# SAMV71_Xplained_Ultra_Audio.net
KiCad netlist of a schematic drawn in Altium Designer
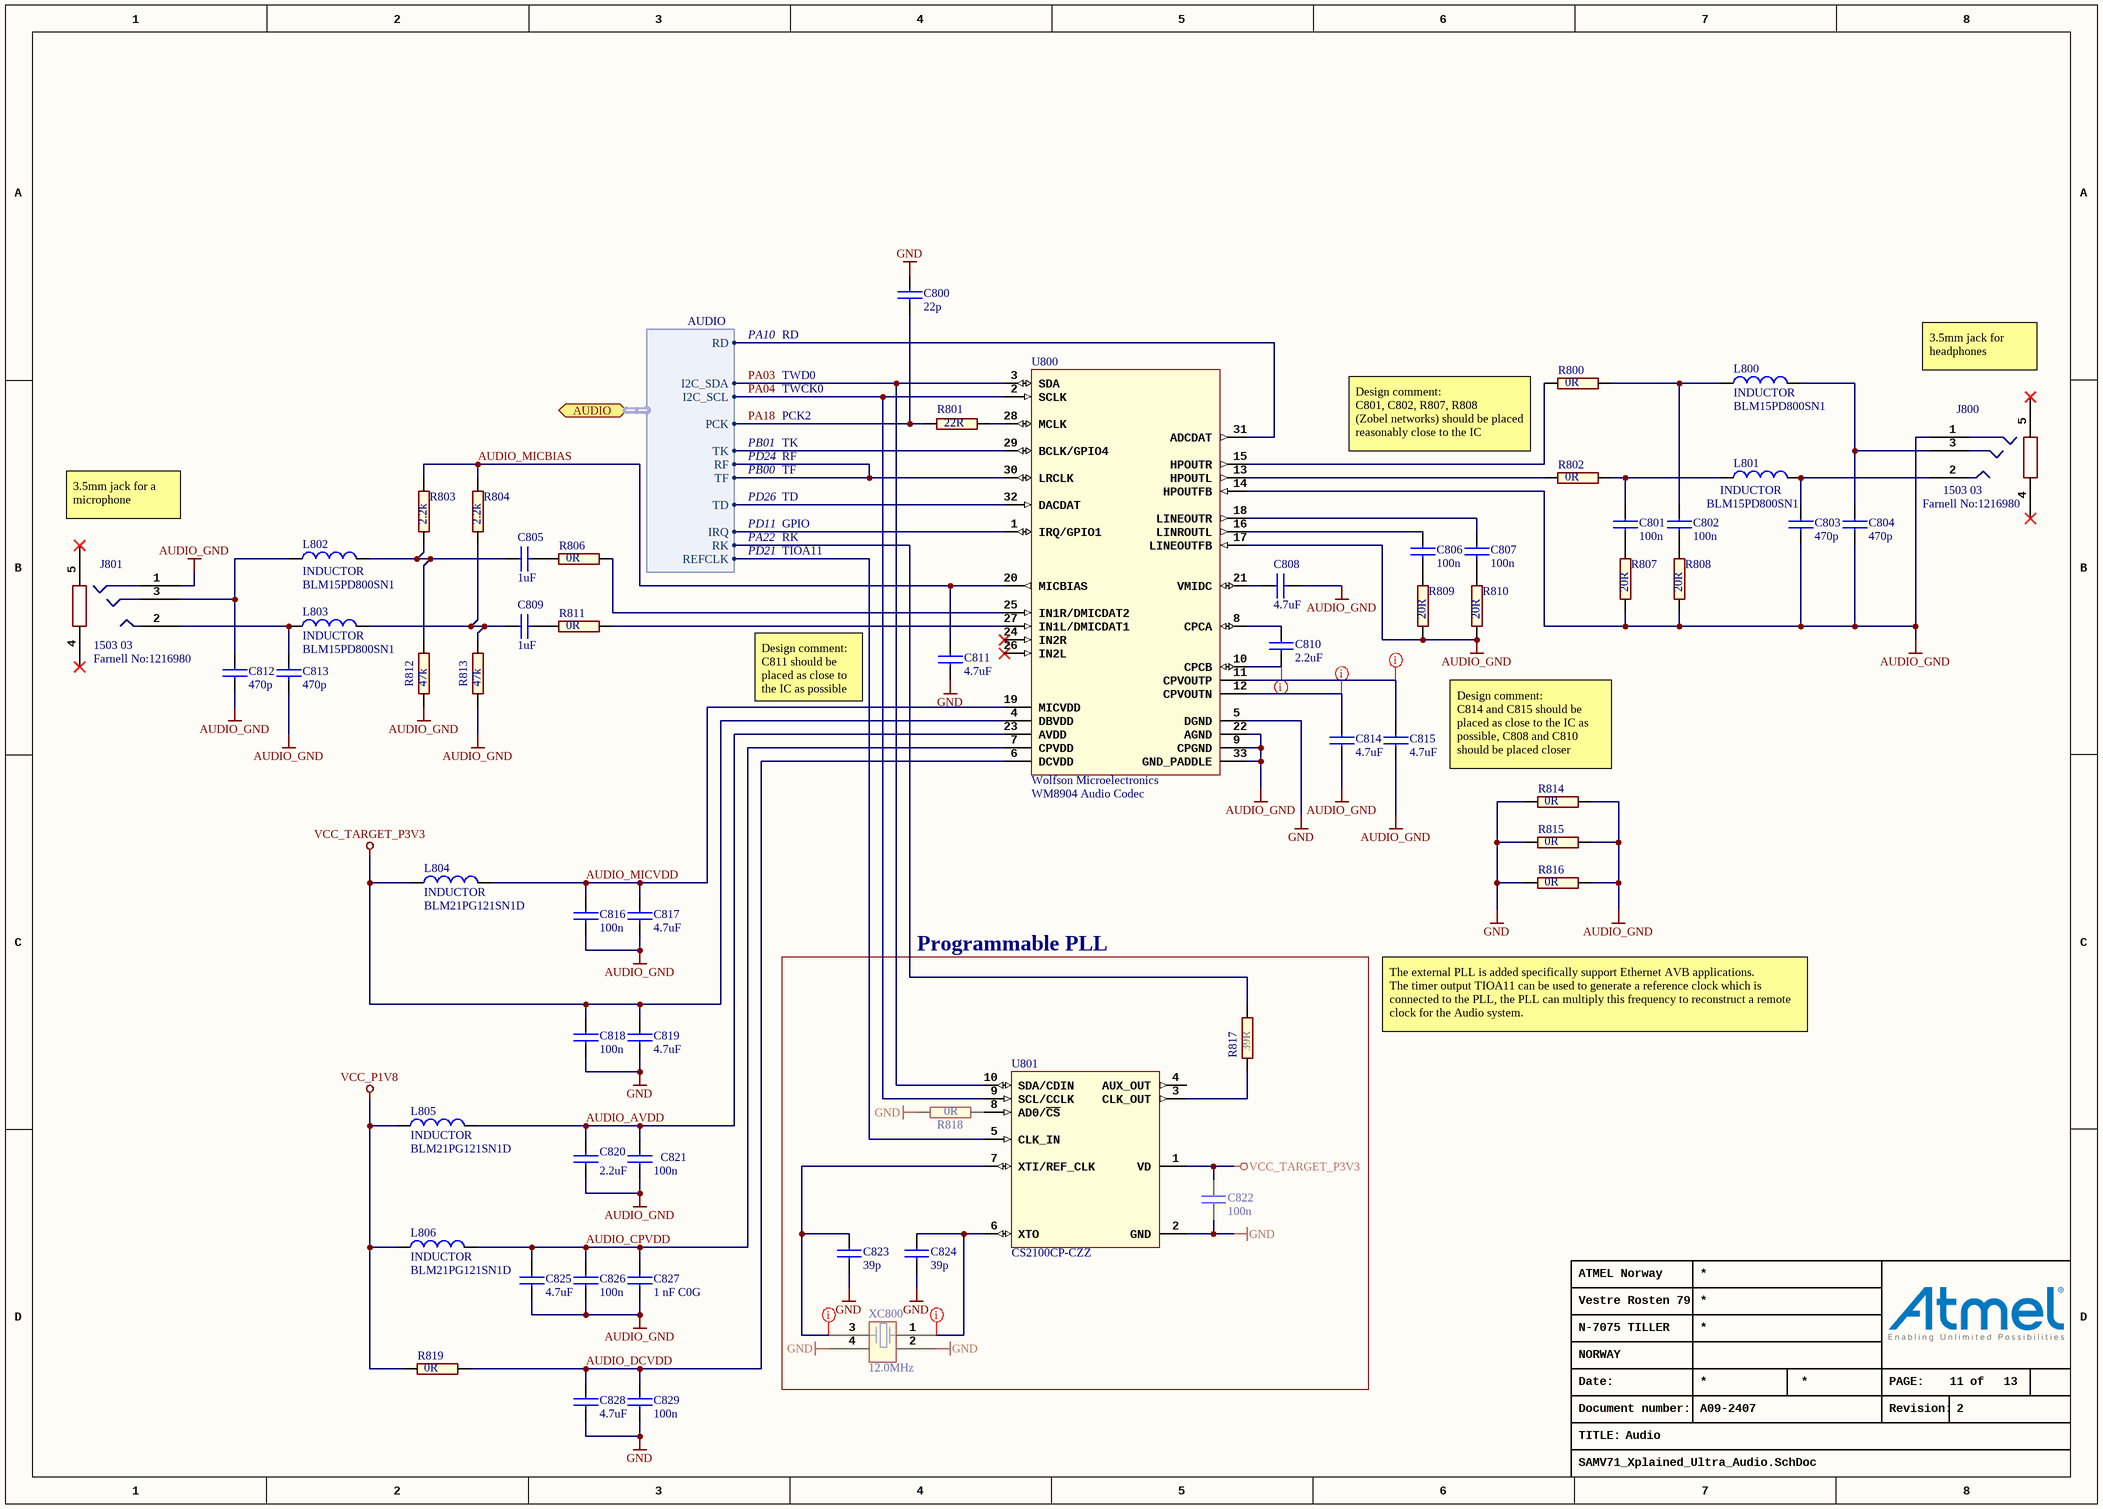
[diagram p0: SAMV71_Xplained_Ultra_Audio.SchDoc]

(export (version "E")
  (design (tool "Eeschema 10.0.6"))
  (components
    (comp (ref "C800")
      (value "22p")
      (footprint "AP1-00001")
      (description "Ceramic capacitor, SMD 0402, NP0, 50V, +/-5%")
      (fields (field (name "TOLERANCE") "50V, +/-5%") (field (name "Comment") "CAP-NONPOL"))
      (libsource (lib "AltiumDbLib") (part "CAP-NONPOL"))
    )
    (comp (ref "C801")
      (value "100n")
      (footprint "AP1-00001")
      (description "Ceramic capacitor, SMD 0402, X7R, 16V, +/-10%")
      (fields (field (name "TOLERANCE") "16V, +/-10%") (field (name "MANUFACTURER") "Kemet"))
      (libsource (lib "AltiumDbLib") (part "CAP-NONPOL"))
    )
    (comp (ref "C802")
      (value "100n")
      (footprint "AP1-00001")
      (description "Ceramic capacitor, SMD 0402, X7R, 16V, +/-10%")
      (fields (field (name "TOLERANCE") "16V, +/-10%") (field (name "MANUFACTURER") "Kemet"))
      (libsource (lib "AltiumDbLib") (part "CAP-NONPOL"))
    )
    (comp (ref "C803")
      (value "470p")
      (footprint "AP1-00001")
      (description "Ceramic capacitor, SMD 0402, X7R, 50V, +/-10%")
      (fields (field (name "TOLERANCE") "50V, +/-10%") (field (name "Comment") "8819904  @ element14"))
      (libsource (lib "AltiumDbLib") (part "CAP-NONPOL"))
    )
    (comp (ref "C804")
      (value "470p")
      (footprint "AP1-00001")
      (description "Ceramic capacitor, SMD 0402, X7R, 50V, +/-10%")
      (fields (field (name "TOLERANCE") "50V, +/-10%") (field (name "Comment") "8819904  @ element14"))
      (libsource (lib "AltiumDbLib") (part "CAP-NONPOL"))
    )
    (comp (ref "C805")
      (value "1uF")
      (footprint "AP1-00038")
      (description "Ceramic capacitor, SMD 0402, X5R, 10V, ±10 %")
      (fields (field (name "MANUFACTURER") "AVX") (field (name "MPN") "0402ZD105KAT2A"))
      (libsource (lib "AltiumDbLib") (part "CAP-NONPOL"))
    )
    (comp (ref "C806")
      (value "100n")
      (footprint "AP1-00001")
      (description "Ceramic capacitor, SMD 0402, X7R, 16V, +/-10%")
      (fields (field (name "TOLERANCE") "16V, +/-10%") (field (name "MANUFACTURER") "Kemet"))
      (libsource (lib "AltiumDbLib") (part "CAP-NONPOL"))
    )
    (comp (ref "C807")
      (value "100n")
      (footprint "AP1-00001")
      (description "Ceramic capacitor, SMD 0402, X7R, 16V, +/-10%")
      (fields (field (name "TOLERANCE") "16V, +/-10%") (field (name "MANUFACTURER") "Kemet"))
      (libsource (lib "AltiumDbLib") (part "CAP-NONPOL"))
    )
    (comp (ref "C808")
      (value "4.7uF")
      (footprint "AP1-00039")
      (description "Ceramic capacitor, SMD 0603, X5R, 10V, 10% (de31036)")
      (fields (field (name "TOLERANCE") "10%") (field (name "MANUFACTURER") "tdk"))
      (libsource (lib "AltiumDbLib") (part "CAP-NONPOL"))
    )
    (comp (ref "C809")
      (value "1uF")
      (footprint "AP1-00038")
      (description "Ceramic capacitor, SMD 0402, X5R, 10V, ±10 %")
      (fields (field (name "MANUFACTURER") "AVX") (field (name "MPN") "0402ZD105KAT2A"))
      (libsource (lib "AltiumDbLib") (part "CAP-NONPOL"))
    )
    (comp (ref "C810")
      (value "2.2uF")
      (footprint "AP1-00001")
      (description "Ceramic capacitor, SMD 0402, X5R, 6.3V, +/-20%")
      (fields (field (name "TOLERANCE") "Â±20%") (field (name "MANUFACTURER") "Kemet"))
      (libsource (lib "AltiumDbLib") (part "CAP-NONPOL"))
    )
    (comp (ref "C811")
      (value "4.7uF")
      (footprint "AP1-00039")
      (description "Ceramic capacitor, SMD 0603, X5R, 10V, 10% (de31036)")
      (fields (field (name "TOLERANCE") "10%") (field (name "MANUFACTURER") "tdk"))
      (libsource (lib "AltiumDbLib") (part "CAP-NONPOL"))
    )
    (comp (ref "C812")
      (value "470p")
      (footprint "AP1-00001")
      (description "Ceramic capacitor, SMD 0402, X7R, 50V, +/-10%")
      (fields (field (name "TOLERANCE") "50V, +/-10%") (field (name "Comment") "CAP-NONPOL"))
      (libsource (lib "AltiumDbLib") (part "CAP-NONPOL"))
    )
    (comp (ref "C813")
      (value "470p")
      (footprint "AP1-00001")
      (description "Ceramic capacitor, SMD 0402, X7R, 50V, +/-10%")
      (fields (field (name "TOLERANCE") "50V, +/-10%") (field (name "Comment") "CAP-NONPOL"))
      (libsource (lib "AltiumDbLib") (part "CAP-NONPOL"))
    )
    (comp (ref "C814")
      (value "4.7uF")
      (footprint "AP1-00001")
      (description "Ceramic capacitor, SMD 0402, X5R, 6.3V, +/-20% (de33687)")
      (fields (field (name "TOLERANCE") "+-20%") (field (name "MANUFACTURER") "Murata"))
      (libsource (lib "AltiumDbLib") (part "CAP-NONPOL"))
    )
    (comp (ref "C815")
      (value "4.7uF")
      (footprint "AP1-00001")
      (description "Ceramic capacitor, SMD 0402, X5R, 6.3V, +/-20% (de33687)")
      (fields (field (name "TOLERANCE") "+-20%") (field (name "MANUFACTURER") "Murata"))
      (libsource (lib "AltiumDbLib") (part "CAP-NONPOL"))
    )
    (comp (ref "C816")
      (value "100n")
      (footprint "AP1-00001")
      (description "Ceramic capacitor, SMD 0402, X7R, 16V, +/-10%")
      (fields (field (name "TOLERANCE") "16V, +/-10%") (field (name "MANUFACTURER") "Kemet"))
      (libsource (lib "AltiumDbLib") (part "CAP-NONPOL"))
    )
    (comp (ref "C817")
      (value "4.7uF")
      (footprint "AP1-00039")
      (description "Ceramic capacitor, SMD 0603, X5R, 10V, 10% (de31036)")
      (fields (field (name "TOLERANCE") "10%") (field (name "MANUFACTURER") "tdk"))
      (libsource (lib "AltiumDbLib") (part "CAP-NONPOL"))
    )
    (comp (ref "C818")
      (value "100n")
      (footprint "AP1-00001")
      (description "Ceramic capacitor, SMD 0402, X7R, 16V, +/-10%")
      (fields (field (name "TOLERANCE") "16V, +/-10%") (field (name "MANUFACTURER") "Kemet"))
      (libsource (lib "AltiumDbLib") (part "CAP-NONPOL"))
    )
    (comp (ref "C819")
      (value "4.7uF")
      (footprint "AP1-00039")
      (description "Ceramic capacitor, SMD 0603, X5R, 10V, 10% (de31036)")
      (fields (field (name "TOLERANCE") "10%") (field (name "MANUFACTURER") "tdk"))
      (libsource (lib "AltiumDbLib") (part "CAP-NONPOL"))
    )
    (comp (ref "C820")
      (value "2.2uF")
      (footprint "AP1-00001")
      (description "Ceramic capacitor, SMD 0402, X5R, 6.3V, +/-20%")
      (fields (field (name "TOLERANCE") "Â±20%") (field (name "MANUFACTURER") "Kemet"))
      (libsource (lib "AltiumDbLib") (part "CAP-NONPOL"))
    )
    (comp (ref "C821")
      (value "100n")
      (footprint "AP1-00001")
      (description "Ceramic capacitor, SMD 0402, X7R, 16V, +/-10%")
      (fields (field (name "TOLERANCE") "16V, +/-10%") (field (name "MANUFACTURER") "Kemet"))
      (libsource (lib "AltiumDbLib") (part "CAP-NONPOL"))
    )
    (comp (ref "C822")
      (value "100n")
      (footprint "AP1-00001")
      (description "Ceramic capacitor, SMD 0402, X7R, 16V, +/-10%")
      (fields (field (name "TOLERANCE") "16V, +/-10%") (field (name "MANUFACTURER") "Kemet"))
      (libsource (lib "AltiumDbLib") (part "CAP-NONPOL"))
    )
    (comp (ref "C823")
      (value "39p")
      (footprint "AP1-00001")
      (description "Ceramic capacitor, SMD 0402, NP0, 50V, +/-5%")
      (fields (field (name "TOLERANCE") "50V, +/-5%") (field (name "Comment") "CAP-NONPOL"))
      (libsource (lib "AltiumDbLib") (part "CAP-NONPOL"))
    )
    (comp (ref "C824")
      (value "39p")
      (footprint "AP1-00001")
      (description "Ceramic capacitor, SMD 0402, NP0, 50V, +/-5%")
      (fields (field (name "TOLERANCE") "50V, +/-5%") (field (name "Comment") "CAP-NONPOL"))
      (libsource (lib "AltiumDbLib") (part "CAP-NONPOL"))
    )
    (comp (ref "C825")
      (value "4.7uF")
      (footprint "AP1-00039")
      (description "Ceramic capacitor, SMD 0603, X5R, 10V, 10% (de31036)")
      (fields (field (name "TOLERANCE") "10%") (field (name "MANUFACTURER") "tdk"))
      (libsource (lib "AltiumDbLib") (part "CAP-NONPOL"))
    )
    (comp (ref "C826")
      (value "100n")
      (footprint "AP1-00001")
      (description "Ceramic capacitor, SMD 0402, X7R, 16V, +/-10%")
      (fields (field (name "TOLERANCE") "16V, +/-10%") (field (name "MANUFACTURER") "Kemet"))
      (libsource (lib "AltiumDbLib") (part "CAP-NONPOL"))
    )
    (comp (ref "C827")
      (value "1 nF C0G")
      (footprint "AP1-00001")
      (description "Ceramic capacitor, SMD 0402, C0G, 50V, +/-5%")
      (fields (field (name "TOLERANCE") "5%") (field (name "MANUFACTURER") "Murata"))
      (libsource (lib "AltiumDbLib") (part "CAP-NONPOL"))
    )
    (comp (ref "C828")
      (value "4.7uF")
      (footprint "AP1-00039")
      (description "Ceramic capacitor, SMD 0603, X5R, 10V, 10% (de31036)")
      (fields (field (name "TOLERANCE") "10%") (field (name "MANUFACTURER") "tdk"))
      (libsource (lib "AltiumDbLib") (part "CAP-NONPOL"))
    )
    (comp (ref "C829")
      (value "100n")
      (footprint "AP1-00001")
      (description "Ceramic capacitor, SMD 0402, X7R, 16V, +/-10%")
      (fields (field (name "TOLERANCE") "16V, +/-10%") (field (name "MANUFACTURER") "Kemet"))
      (libsource (lib "AltiumDbLib") (part "CAP-NONPOL"))
    )
    (comp (ref "J800")
      (value "Farnell No:1216980")
      (footprint "AP8-00397")
      (description "3.5mm stereo phone jack")
      (fields
        (field (name "ALTIUM_VALUE") "1503 03")
        (field (name "MANUFACTURER") "Lumberg")
        (field (name "MPN") "1503 03")
      )
      (libsource (lib "AltiumDbLib") (part "Jack_Stereo_1503_03"))
    )
    (comp (ref "J801")
      (value "Farnell No:1216980")
      (footprint "AP8-00397")
      (description "3.5mm stereo phone jack")
      (fields
        (field (name "ALTIUM_VALUE") "1503 03")
        (field (name "MANUFACTURER") "Lumberg")
        (field (name "MPN") "1503 03")
      )
      (libsource (lib "") (part "Jack_Stereo_1503_03_1"))
    )
    (comp (ref "L800")
      (value "INDUCTOR")
      (footprint "AP3-00028")
      (description "FERRITE CHIP 80 OHM 1500MA 0402")
      (fields
        (field (name "ALTIUM_VALUE") "BLM15PD800SN1")
        (field (name "TOLERANCE") "±25%")
        (field (name "MANUFACTURER") "Murata")
      )
      (libsource (lib "AltiumDbLib") (part "INDUCTOR"))
    )
    (comp (ref "L801")
      (value "INDUCTOR")
      (footprint "AP3-00028")
      (description "FERRITE CHIP 80 OHM 1500MA 0402")
      (fields
        (field (name "ALTIUM_VALUE") "BLM15PD800SN1")
        (field (name "TOLERANCE") "±25%")
        (field (name "MANUFACTURER") "Murata")
      )
      (libsource (lib "AltiumDbLib") (part "INDUCTOR"))
    )
    (comp (ref "L802")
      (value "INDUCTOR")
      (footprint "AP3-00028")
      (description "FERRITE CHIP 80 OHM 1500MA 0402")
      (fields
        (field (name "ALTIUM_VALUE") "BLM15PD800SN1")
        (field (name "TOLERANCE") "±25%")
        (field (name "MANUFACTURER") "Murata")
      )
      (libsource (lib "AltiumDbLib") (part "INDUCTOR"))
    )
    (comp (ref "L803")
      (value "INDUCTOR")
      (footprint "AP3-00028")
      (description "FERRITE CHIP 80 OHM 1500MA 0402")
      (fields
        (field (name "ALTIUM_VALUE") "BLM15PD800SN1")
        (field (name "TOLERANCE") "±25%")
        (field (name "MANUFACTURER") "Murata")
      )
      (libsource (lib "AltiumDbLib") (part "INDUCTOR"))
    )
    (comp (ref "L804")
      (value "INDUCTOR")
      (footprint "AP3-00104")
      (fields
        (field (name "ALTIUM_VALUE") "BLM21PG121SN1D")
        (field (name "MANUFACTURER") "Murata")
        (field (name "MPN") "BLM21PG121SN1D")
      )
      (libsource (lib "AltiumDbLib") (part "INDUCTOR"))
    )
    (comp (ref "L805")
      (value "INDUCTOR")
      (footprint "AP3-00104")
      (fields
        (field (name "ALTIUM_VALUE") "BLM21PG121SN1D")
        (field (name "MANUFACTURER") "Murata")
        (field (name "MPN") "BLM21PG121SN1D")
      )
      (libsource (lib "AltiumDbLib") (part "INDUCTOR"))
    )
    (comp (ref "L806")
      (value "INDUCTOR")
      (footprint "AP3-00104")
      (fields
        (field (name "ALTIUM_VALUE") "BLM21PG121SN1D")
        (field (name "MANUFACTURER") "Murata")
        (field (name "MPN") "BLM21PG121SN1D")
      )
      (libsource (lib "AltiumDbLib") (part "INDUCTOR"))
    )
    (comp (ref "R800")
      (value "0R")
      (footprint "AP2-00000")
      (description "RES 0.0 OHM 1/16W 0402 SMD")
      (fields (field (name "TOLERANCE") "1 %") (field (name "MANUFACTURER") "(n/a)"))
      (libsource (lib "AltiumDbLib") (part "R2"))
    )
    (comp (ref "R801")
      (value "22R")
      (footprint "AP2-00000")
      (description "Thick film resistor, SMD 0402, 1/16W, 1% (de23607)")
      (fields (field (name "TOLERANCE") "1 %") (field (name "MANUFACTURER") "Samsung"))
      (libsource (lib "AltiumDbLib") (part "R2"))
    )
    (comp (ref "R802")
      (value "0R")
      (footprint "AP2-00000")
      (description "RES 0.0 OHM 1/16W 0402 SMD")
      (fields (field (name "TOLERANCE") "1 %") (field (name "MANUFACTURER") "(n/a)"))
      (libsource (lib "AltiumDbLib") (part "R2"))
    )
    (comp (ref "R803")
      (value "2.2k")
      (footprint "AP2-00000")
      (description "Thick film resistor, SMD 0402, 1/16W, 1%")
      (fields (field (name "TOLERANCE") "1 %") (field (name "Comment") "R2"))
      (libsource (lib "") (part "R2_1"))
    )
    (comp (ref "R804")
      (value "2.2k")
      (footprint "AP2-00000")
      (description "Thick film resistor, SMD 0402, 1/16W, 1%")
      (fields (field (name "TOLERANCE") "1 %") (field (name "Comment") "R2"))
      (libsource (lib "") (part "R2_1"))
    )
    (comp (ref "R806")
      (value "0R")
      (footprint "AP2-00000")
      (description "RES 0.0 OHM 1/16W 0402 SMD")
      (fields (field (name "TOLERANCE") "1 %") (field (name "MANUFACTURER") "(n/a)"))
      (libsource (lib "AltiumDbLib") (part "R2"))
    )
    (comp (ref "R807")
      (value "20R")
      (footprint "AP2-00000")
      (description "Thick film resistor, SMD 0402, 1/16W, 1%")
      (fields (field (name "TOLERANCE") "1 %") (field (name "Comment") "R2"))
      (libsource (lib "") (part "R2_1"))
    )
    (comp (ref "R808")
      (value "20R")
      (footprint "AP2-00000")
      (description "Thick film resistor, SMD 0402, 1/16W, 1%")
      (fields (field (name "TOLERANCE") "1 %") (field (name "Comment") "R2"))
      (libsource (lib "") (part "R2_1"))
    )
    (comp (ref "R809")
      (value "20R")
      (footprint "AP2-00000")
      (description "Thick film resistor, SMD 0402, 1/16W, 1%")
      (fields (field (name "TOLERANCE") "1 %") (field (name "Comment") "R2"))
      (libsource (lib "") (part "R2_1"))
    )
    (comp (ref "R810")
      (value "20R")
      (footprint "AP2-00000")
      (description "Thick film resistor, SMD 0402, 1/16W, 1%")
      (fields (field (name "TOLERANCE") "1 %") (field (name "Comment") "R2"))
      (libsource (lib "") (part "R2_1"))
    )
    (comp (ref "R811")
      (value "0R")
      (footprint "AP2-00000")
      (description "RES 0.0 OHM 1/16W 0402 SMD")
      (fields (field (name "TOLERANCE") "1 %") (field (name "MANUFACTURER") "(n/a)"))
      (libsource (lib "AltiumDbLib") (part "R2"))
    )
    (comp (ref "R812")
      (value "47k")
      (footprint "AP2-00000")
      (description "Thick film resistor, SMD 0402, 1/16W, 1%")
      (fields (field (name "TOLERANCE") "1 %") (field (name "Comment") "R2"))
      (libsource (lib "") (part "R2_1"))
    )
    (comp (ref "R813")
      (value "47k")
      (footprint "AP2-00000")
      (description "Thick film resistor, SMD 0402, 1/16W, 1%")
      (fields (field (name "TOLERANCE") "1 %") (field (name "Comment") "R2"))
      (libsource (lib "") (part "R2_1"))
    )
    (comp (ref "R814")
      (value "0R")
      (footprint "AP2-00000")
      (description "RES 0.0 OHM 1/16W 0402 SMD")
      (fields (field (name "TOLERANCE") "1 %") (field (name "MANUFACTURER") "(n/a)"))
      (libsource (lib "AltiumDbLib") (part "R2"))
    )
    (comp (ref "R815")
      (value "0R")
      (footprint "AP2-00000")
      (description "RES 0.0 OHM 1/16W 0402 SMD")
      (fields (field (name "TOLERANCE") "1 %") (field (name "MANUFACTURER") "(n/a)"))
      (libsource (lib "AltiumDbLib") (part "R2"))
    )
    (comp (ref "R816")
      (value "0R")
      (footprint "AP2-00000")
      (description "RES 0.0 OHM 1/16W 0402 SMD")
      (fields (field (name "TOLERANCE") "1 %") (field (name "MANUFACTURER") "(n/a)"))
      (libsource (lib "AltiumDbLib") (part "R2"))
    )
    (comp (ref "R817")
      (value "39R")
      (footprint "AP2-00000")
      (description "Thick film resistor, SMD 0402, 1/16W, 1%")
      (fields (field (name "TOLERANCE") "1 %") (field (name "Comment") "R2"))
      (libsource (lib "") (part "R2_1"))
    )
    (comp (ref "R818")
      (value "0R")
      (footprint "AP2-00000")
      (description "RES 0.0 OHM 1/16W 0402 SMD")
      (fields (field (name "TOLERANCE") "1 %") (field (name "MANUFACTURER") "(n/a)"))
      (libsource (lib "AltiumDbLib") (part "R2"))
    )
    (comp (ref "R819")
      (value "0R")
      (footprint "AP2-00000")
      (description "RES 0.0 OHM 1/16W 0402 SMD")
      (fields (field (name "TOLERANCE") "1 %") (field (name "MANUFACTURER") "(n/a)"))
      (libsource (lib "AltiumDbLib") (part "R2"))
    )
    (comp (ref "U800")
      (value "Wolfson Microelectronics")
      (footprint "AP6-00420")
      (description "Ultra Low Power Codec for Portable Audio Applications")
      (fields (field (name "ALTIUM_VALUE") "WM8904 Audio Codec"))
      (libsource (lib "AltiumDbLib") (part "WM8904"))
    )
    (comp (ref "U801")
      (value "CS2100CP-CZZ")
      (footprint "AP6-00097")
      (description "Programmable Phase-Locked Loop Clock Generator")
      (fields (field (name "Comment") "CS2100"))
      (libsource (lib "AltiumDbLib") (part "CS2100"))
    )
    (comp (ref "XC800")
      (value "12.0MHz")
      (footprint "AP7-00039")
      (description "Fox FQ5032B 12.0MHz SMD crystal 738B-12")
      (fields (field (name "TOLERANCE") "30PPM") (field (name "MANUFACTURER") "Fox  Electronics"))
      (libsource (lib "AltiumDbLib") (part "CRYSTAL1324"))
    )
  )
  (nets
    (net (code "2") (name "/AUDIO_AVDD") (class "Default")
      (node (ref "C820") (pin "1") (pinfunction "1_1") (pintype "passive"))
      (node (ref "C821") (pin "1") (pinfunction "1_1") (pintype "passive"))
      (node (ref "L805") (pin "2") (pinfunction "2_2") (pintype "passive"))
      (node (ref "U800") (pin "23") (pinfunction "AVDD_23") (pintype "power_in"))
    )
    (net (code "3") (name "/AUDIO_CPVDD") (class "Default")
      (node (ref "C825") (pin "1") (pinfunction "1_1") (pintype "passive"))
      (node (ref "C826") (pin "1") (pinfunction "1_1") (pintype "passive"))
      (node (ref "C827") (pin "1") (pinfunction "1_1") (pintype "passive"))
      (node (ref "L806") (pin "2") (pinfunction "2_2") (pintype "passive"))
      (node (ref "U800") (pin "7") (pinfunction "CPVDD_7") (pintype "power_in"))
    )
    (net (code "4") (name "/AUDIO_DCVDD") (class "Default")
      (node (ref "C828") (pin "1") (pinfunction "1_1") (pintype "passive"))
      (node (ref "C829") (pin "1") (pinfunction "1_1") (pintype "passive"))
      (node (ref "R819") (pin "2") (pinfunction "2_2") (pintype "passive"))
      (node (ref "U800") (pin "6") (pinfunction "DCVDD_6") (pintype "power_in"))
    )
    (net (code "5") (name "/AUDIO_MICBIAS") (class "Default")
      (node (ref "C811") (pin "1") (pinfunction "1_1") (pintype "passive"))
      (node (ref "R803") (pin "2") (pinfunction "2_2") (pintype "passive"))
      (node (ref "R804") (pin "2") (pinfunction "2_2") (pintype "passive"))
      (node (ref "U800") (pin "20") (pinfunction "MICBIAS_20") (pintype "output"))
    )
    (net (code "6") (name "/AUDIO_MICVDD") (class "Default")
      (node (ref "C816") (pin "1") (pinfunction "1_1") (pintype "passive"))
      (node (ref "C817") (pin "1") (pinfunction "1_1") (pintype "passive"))
      (node (ref "L804") (pin "2") (pinfunction "2_2") (pintype "passive"))
      (node (ref "U800") (pin "19") (pinfunction "MICVDD_19") (pintype "power_in"))
    )
    (net (code "7") (name "/IRQ") (class "Default")
      (node (ref "U800") (pin "1") (pinfunction "IRQ/GPIO1_1") (pintype "bidirectional"))
    )
    (net (code "8") (name "/PA03") (class "Default")
      (node (ref "U800") (pin "3") (pinfunction "SDA_3") (pintype "bidirectional"))
      (node (ref "U801") (pin "10") (pinfunction "SDA/CDIN_10") (pintype "bidirectional"))
    )
    (net (code "9") (name "/PA04") (class "Default")
      (node (ref "U800") (pin "2") (pinfunction "SCLK_2") (pintype "input"))
      (node (ref "U801") (pin "9") (pinfunction "SCL/CCLK_9") (pintype "input"))
    )
    (net (code "10") (name "/PA18") (class "Default")
      (node (ref "C800") (pin "2") (pinfunction "2_2") (pintype "passive"))
      (node (ref "R801") (pin "1") (pinfunction "1_1") (pintype "passive"))
    )
    (net (code "11") (name "/RD") (class "Default")
      (node (ref "U800") (pin "31") (pinfunction "ADCDAT_31") (pintype "output"))
    )
    (net (code "12") (name "/REFCLK") (class "Default")
      (node (ref "U801") (pin "5") (pinfunction "CLK_IN_5") (pintype "input"))
    )
    (net (code "13") (name "/RF") (class "Default")
      (node (ref "U800") (pin "30") (pinfunction "LRCLK_30") (pintype "bidirectional"))
    )
    (net (code "14") (name "/RK") (class "Default")
      (node (ref "R817") (pin "2") (pinfunction "2_2") (pintype "passive"))
    )
    (net (code "15") (name "/TD") (class "Default")
      (node (ref "U800") (pin "32") (pinfunction "DACDAT_32") (pintype "input"))
    )
    (net (code "16") (name "/TK") (class "Default")
      (node (ref "U800") (pin "29") (pinfunction "BCLK/GPIO4_29") (pintype "bidirectional"))
    )
    (net (code "18") (name "AUDIO_GND") (class "Default")
      (node (ref "C803") (pin "2") (pinfunction "2_2") (pintype "passive"))
      (node (ref "C804") (pin "2") (pinfunction "2_2") (pintype "passive"))
      (node (ref "C808") (pin "2") (pinfunction "2_2") (pintype "passive"))
      (node (ref "C812") (pin "2") (pinfunction "2_2") (pintype "passive"))
      (node (ref "C813") (pin "2") (pinfunction "2_2") (pintype "passive"))
      (node (ref "C814") (pin "2") (pinfunction "2_2") (pintype "passive"))
      (node (ref "C815") (pin "2") (pinfunction "2_2") (pintype "passive"))
      (node (ref "C816") (pin "2") (pinfunction "2_2") (pintype "passive"))
      (node (ref "C817") (pin "2") (pinfunction "2_2") (pintype "passive"))
      (node (ref "C820") (pin "2") (pinfunction "2_2") (pintype "passive"))
      (node (ref "C821") (pin "2") (pinfunction "2_2") (pintype "passive"))
      (node (ref "C825") (pin "2") (pinfunction "2_2") (pintype "passive"))
      (node (ref "C826") (pin "2") (pinfunction "2_2") (pintype "passive"))
      (node (ref "C827") (pin "2") (pinfunction "2_2") (pintype "passive"))
      (node (ref "J800") (pin "1") (pinfunction "GND_1") (pintype "passive"))
      (node (ref "J801") (pin "1") (pinfunction "GND_1") (pintype "passive"))
      (node (ref "R807") (pin "1") (pinfunction "1_1") (pintype "passive"))
      (node (ref "R808") (pin "1") (pinfunction "1_1") (pintype "passive"))
      (node (ref "R809") (pin "1") (pinfunction "1_1") (pintype "passive"))
      (node (ref "R810") (pin "1") (pinfunction "1_1") (pintype "passive"))
      (node (ref "R812") (pin "1") (pinfunction "1_1") (pintype "passive"))
      (node (ref "R813") (pin "1") (pinfunction "1_1") (pintype "passive"))
      (node (ref "R814") (pin "2") (pinfunction "2_2") (pintype "passive"))
      (node (ref "R815") (pin "2") (pinfunction "2_2") (pintype "passive"))
      (node (ref "R816") (pin "2") (pinfunction "2_2") (pintype "passive"))
      (node (ref "U800") (pin "14") (pinfunction "HPOUTFB_14") (pintype "input"))
      (node (ref "U800") (pin "17") (pinfunction "LINEOUTFB_17") (pintype "input"))
      (node (ref "U800") (pin "22") (pinfunction "AGND_22") (pintype "power_in"))
      (node (ref "U800") (pin "33") (pinfunction "GND_PADDLE_33") (pintype "power_in"))
      (node (ref "U800") (pin "9") (pinfunction "CPGND_9") (pintype "power_in"))
    )
    (net (code "19") (name "GND") (class "Default")
      (node (ref "C800") (pin "1") (pinfunction "1_1") (pintype "passive"))
      (node (ref "C811") (pin "2") (pinfunction "2_2") (pintype "passive"))
      (node (ref "C818") (pin "2") (pinfunction "2_2") (pintype "passive"))
      (node (ref "C819") (pin "2") (pinfunction "2_2") (pintype "passive"))
      (node (ref "C822") (pin "2") (pinfunction "2_2") (pintype "passive"))
      (node (ref "C823") (pin "2") (pinfunction "2_2") (pintype "passive"))
      (node (ref "C824") (pin "2") (pinfunction "2_2") (pintype "passive"))
      (node (ref "C828") (pin "2") (pinfunction "2_2") (pintype "passive"))
      (node (ref "C829") (pin "2") (pinfunction "2_2") (pintype "passive"))
      (node (ref "R814") (pin "1") (pinfunction "1_1") (pintype "passive"))
      (node (ref "R815") (pin "1") (pinfunction "1_1") (pintype "passive"))
      (node (ref "R816") (pin "1") (pinfunction "1_1") (pintype "passive"))
      (node (ref "R818") (pin "1") (pinfunction "1_1") (pintype "passive"))
      (node (ref "U800") (pin "5") (pinfunction "DGND_5") (pintype "power_in"))
      (node (ref "U801") (pin "2") (pinfunction "GND_2") (pintype "power_in"))
      (node (ref "XC800") (pin "2") (pinfunction "2_2") (pintype "passive"))
      (node (ref "XC800") (pin "4") (pinfunction "4_4") (pintype "passive"))
    )
    (net (code "20") (name "Net-(C801-Pad1)") (class "Default")
      (node (ref "C801") (pin "1") (pinfunction "1_1") (pintype "passive"))
      (node (ref "L801") (pin "1") (pinfunction "1_1") (pintype "passive"))
      (node (ref "R802") (pin "2") (pinfunction "2_2") (pintype "passive"))
    )
    (net (code "21") (name "Net-(C801-Pad2)") (class "Default")
      (node (ref "C801") (pin "2") (pinfunction "2_2") (pintype "passive"))
      (node (ref "R807") (pin "2") (pinfunction "2_2") (pintype "passive"))
    )
    (net (code "22") (name "Net-(C802-Pad1)") (class "Default")
      (node (ref "C802") (pin "1") (pinfunction "1_1") (pintype "passive"))
      (node (ref "L800") (pin "1") (pinfunction "1_1") (pintype "passive"))
      (node (ref "R800") (pin "2") (pinfunction "2_2") (pintype "passive"))
    )
    (net (code "23") (name "Net-(C802-Pad2)") (class "Default")
      (node (ref "C802") (pin "2") (pinfunction "2_2") (pintype "passive"))
      (node (ref "R808") (pin "2") (pinfunction "2_2") (pintype "passive"))
    )
    (net (code "24") (name "Net-(C803-Pad1)") (class "Default")
      (node (ref "C803") (pin "1") (pinfunction "1_1") (pintype "passive"))
      (node (ref "J800") (pin "2") (pintype "passive"))
      (node (ref "L801") (pin "2") (pinfunction "2_2") (pintype "passive"))
    )
    (net (code "25") (name "Net-(C804-Pad1)") (class "Default")
      (node (ref "C804") (pin "1") (pinfunction "1_1") (pintype "passive"))
      (node (ref "J800") (pin "3") (pintype "passive"))
      (node (ref "L800") (pin "2") (pinfunction "2_2") (pintype "passive"))
    )
    (net (code "26") (name "Net-(C805-Pad1)") (class "Default")
      (node (ref "C805") (pin "1") (pinfunction "1_1") (pintype "passive"))
      (node (ref "L802") (pin "2") (pinfunction "2_2") (pintype "passive"))
      (node (ref "R803") (pin "1") (pinfunction "1_1") (pintype "passive"))
      (node (ref "R812") (pin "2") (pinfunction "2_2") (pintype "passive"))
    )
    (net (code "27") (name "Net-(C805-Pad2)") (class "Default")
      (node (ref "C805") (pin "2") (pinfunction "2_2") (pintype "passive"))
      (node (ref "R806") (pin "1") (pinfunction "1_1") (pintype "passive"))
    )
    (net (code "28") (name "Net-(C806-Pad2)") (class "Default")
      (node (ref "C806") (pin "2") (pinfunction "2_2") (pintype "passive"))
      (node (ref "R809") (pin "2") (pinfunction "2_2") (pintype "passive"))
    )
    (net (code "29") (name "Net-(C807-Pad2)") (class "Default")
      (node (ref "C807") (pin "2") (pinfunction "2_2") (pintype "passive"))
      (node (ref "R810") (pin "2") (pinfunction "2_2") (pintype "passive"))
    )
    (net (code "30") (name "Net-(C809-Pad1)") (class "Default")
      (node (ref "C809") (pin "1") (pinfunction "1_1") (pintype "passive"))
      (node (ref "L803") (pin "2") (pinfunction "2_2") (pintype "passive"))
      (node (ref "R804") (pin "1") (pinfunction "1_1") (pintype "passive"))
      (node (ref "R813") (pin "2") (pinfunction "2_2") (pintype "passive"))
    )
    (net (code "31") (name "Net-(C809-Pad2)") (class "Default")
      (node (ref "C809") (pin "2") (pinfunction "2_2") (pintype "passive"))
      (node (ref "R811") (pin "1") (pinfunction "1_1") (pintype "passive"))
    )
    (net (code "32") (name "Net-(C812-Pad1)") (class "Default")
      (node (ref "C812") (pin "1") (pinfunction "1_1") (pintype "passive"))
      (node (ref "J801") (pin "3") (pintype "passive"))
      (node (ref "L802") (pin "1") (pinfunction "1_1") (pintype "passive"))
    )
    (net (code "33") (name "Net-(C813-Pad1)") (class "Default")
      (node (ref "C813") (pin "1") (pinfunction "1_1") (pintype "passive"))
      (node (ref "J801") (pin "2") (pintype "passive"))
      (node (ref "L803") (pin "1") (pinfunction "1_1") (pintype "passive"))
    )
    (net (code "34") (name "Net-(U800-CPCA)") (class "Default")
      (node (ref "C810") (pin "1") (pinfunction "1_1") (pintype "passive"))
      (node (ref "U800") (pin "8") (pinfunction "CPCA_8") (pintype "bidirectional"))
    )
    (net (code "35") (name "Net-(U800-CPCB)") (class "Default")
      (node (ref "C810") (pin "2") (pinfunction "2_2") (pintype "passive"))
      (node (ref "U800") (pin "10") (pinfunction "CPCB_10") (pintype "bidirectional"))
    )
    (net (code "36") (name "Net-(U800-CPVOUTN)") (class "Default")
      (node (ref "C814") (pin "1") (pinfunction "1_1") (pintype "passive"))
      (node (ref "U800") (pin "12") (pinfunction "CPVOUTN_12") (pintype "passive"))
    )
    (net (code "37") (name "Net-(U800-CPVOUTP)") (class "Default")
      (node (ref "C815") (pin "1") (pinfunction "1_1") (pintype "passive"))
      (node (ref "U800") (pin "11") (pinfunction "CPVOUTP_11") (pintype "passive"))
    )
    (net (code "38") (name "Net-(U800-HPOUTL)") (class "Default")
      (node (ref "R802") (pin "1") (pinfunction "1_1") (pintype "passive"))
      (node (ref "U800") (pin "13") (pinfunction "HPOUTL_13") (pintype "output"))
    )
    (net (code "39") (name "Net-(U800-HPOUTR)") (class "Default")
      (node (ref "R800") (pin "1") (pinfunction "1_1") (pintype "passive"))
      (node (ref "U800") (pin "15") (pinfunction "HPOUTR_15") (pintype "output"))
    )
    (net (code "40") (name "Net-(U800-IN1L{slash}DMICDAT1)") (class "Default")
      (node (ref "R811") (pin "2") (pinfunction "2_2") (pintype "passive"))
      (node (ref "U800") (pin "27") (pinfunction "IN1L/DMICDAT1_27") (pintype "input"))
    )
    (net (code "41") (name "Net-(U800-IN1R{slash}DMICDAT2)") (class "Default")
      (node (ref "R806") (pin "2") (pinfunction "2_2") (pintype "passive"))
      (node (ref "U800") (pin "25") (pinfunction "IN1R/DMICDAT2_25") (pintype "input"))
    )
    (net (code "42") (name "Net-(U800-LINEOUTR)") (class "Default")
      (node (ref "C807") (pin "1") (pinfunction "1_1") (pintype "passive"))
      (node (ref "U800") (pin "18") (pinfunction "LINEOUTR_18") (pintype "output"))
    )
    (net (code "43") (name "Net-(U800-LINROUTL)") (class "Default")
      (node (ref "C806") (pin "1") (pinfunction "1_1") (pintype "passive"))
      (node (ref "U800") (pin "16") (pinfunction "LINROUTL_16") (pintype "output"))
    )
    (net (code "44") (name "Net-(U800-MCLK)") (class "Default")
      (node (ref "R801") (pin "2") (pinfunction "2_2") (pintype "passive"))
      (node (ref "U800") (pin "28") (pinfunction "MCLK_28") (pintype "bidirectional"))
    )
    (net (code "45") (name "Net-(U800-VMIDC)") (class "Default")
      (node (ref "C808") (pin "1") (pinfunction "1_1") (pintype "passive"))
      (node (ref "U800") (pin "21") (pinfunction "VMIDC_21") (pintype "bidirectional"))
    )
    (net (code "46") (name "Net-(U801-AD0{slash}~{CS})") (class "Default")
      (node (ref "R818") (pin "2") (pinfunction "2_2") (pintype "passive"))
      (node (ref "U801") (pin "8") (pinfunction "AD0/~{CS}_8") (pintype "input"))
    )
    (net (code "47") (name "Net-(U801-CLK_OUT)") (class "Default")
      (node (ref "R817") (pin "1") (pinfunction "1_1") (pintype "passive"))
      (node (ref "U801") (pin "3") (pinfunction "CLK_OUT_3") (pintype "output"))
    )
    (net (code "48") (name "Net-(U801-XTI{slash}REF_CLK)") (class "Default")
      (node (ref "C823") (pin "1") (pinfunction "1_1") (pintype "passive"))
      (node (ref "U801") (pin "7") (pinfunction "XTI/REF_CLK_7") (pintype "bidirectional"))
      (node (ref "XC800") (pin "3") (pinfunction "3_3") (pintype "passive"))
    )
    (net (code "49") (name "Net-(U801-XTO)") (class "Default")
      (node (ref "C824") (pin "1") (pinfunction "1_1") (pintype "passive"))
      (node (ref "U801") (pin "6") (pinfunction "XTO_6") (pintype "bidirectional"))
      (node (ref "XC800") (pin "1") (pinfunction "1_1") (pintype "passive"))
    )
    (net (code "50") (name "VCC_P1V8") (class "Default")
      (node (ref "L805") (pin "1") (pinfunction "1_1") (pintype "passive"))
      (node (ref "L806") (pin "1") (pinfunction "1_1") (pintype "passive"))
      (node (ref "R819") (pin "1") (pinfunction "1_1") (pintype "passive"))
    )
    (net (code "51") (name "VCC_TARGET_P3V3") (class "Default")
      (node (ref "C818") (pin "1") (pinfunction "1_1") (pintype "passive"))
      (node (ref "C819") (pin "1") (pinfunction "1_1") (pintype "passive"))
      (node (ref "C822") (pin "1") (pinfunction "1_1") (pintype "passive"))
      (node (ref "L804") (pin "1") (pinfunction "1_1") (pintype "passive"))
      (node (ref "U800") (pin "4") (pinfunction "DBVDD_4") (pintype "power_in"))
      (node (ref "U801") (pin "1") (pinfunction "VD_1") (pintype "power_in"))
    )
    (net (code "52") (name "unconnected-(J800-Pad4)") (class "Default")
      (node (ref "J800") (pin "4") (pintype "passive+no_connect"))
    )
    (net (code "53") (name "unconnected-(J800-Pad5)") (class "Default")
      (node (ref "J800") (pin "5") (pintype "passive+no_connect"))
    )
    (net (code "54") (name "unconnected-(J801-Pad4)") (class "Default")
      (node (ref "J801") (pin "4") (pintype "passive+no_connect"))
    )
    (net (code "55") (name "unconnected-(J801-Pad5)") (class "Default")
      (node (ref "J801") (pin "5") (pintype "passive+no_connect"))
    )
    (net (code "56") (name "unconnected-(U800-IN2L-Pad26)") (class "Default")
      (node (ref "U800") (pin "26") (pinfunction "IN2L_26") (pintype "input+no_connect"))
    )
    (net (code "57") (name "unconnected-(U800-IN2R-Pad24)") (class "Default")
      (node (ref "U800") (pin "24") (pinfunction "IN2R_24") (pintype "input+no_connect"))
    )
    (net (code "58") (name "unconnected-(U801-AUX_OUT-Pad4)") (class "Default")
      (node (ref "U801") (pin "4") (pinfunction "AUX_OUT_4") (pintype "output"))
    )
  )
)
